# VNP.net
KiCad netlist of a schematic drawn in EAGLE
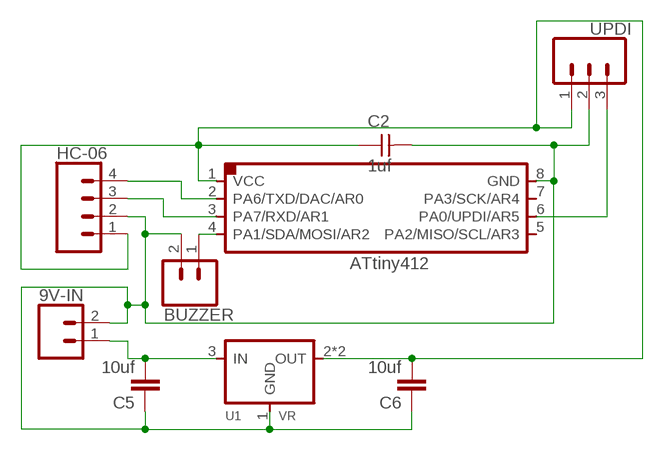
[diagram p0: schematic, sheet 1]

(export (version "E")
  (design (tool "Eeschema 10.0.6"))
  (components
    (comp (ref "9V-IN")
      (value "CONN_02PTH3")
      (footprint "eagle-import:1X02_LONGPADS")
      (libsource (lib "eagle-import") (part "CONN_02PTH3"))
    )
    (comp (ref "BUZZER")
      (value "CONN_02LOCK_LONGPADS")
      (footprint "eagle-import:1X02_LOCK_LONGPADS")
      (libsource (lib "eagle-import") (part "CONN_02LOCK_LONGPADS"))
    )
    (comp (ref "C2")
      (value "1uf")
      (footprint "eagle-import:C1206")
      (libsource (lib "eagle-import") (part "CAP_UNPOLARIZED"))
    )
    (comp (ref "C5")
      (value "10uf")
      (footprint "eagle-import:1206")
      (libsource (lib "eagle-import") (part "CAP1206"))
    )
    (comp (ref "C6")
      (value "10uf")
      (footprint "eagle-import:1206")
      (libsource (lib "eagle-import") (part "CAP1206"))
    )
    (comp (ref "HC-06")
      (value "CONN_04POLAR")
      (footprint "eagle-import:MOLEX-1X4")
      (libsource (lib "eagle-import") (part "CONN_04POLAR"))
    )
    (comp (ref "U$1")
      (value "UC_ATTINY412SI")
      (footprint "eagle-import:SOIC8")
      (libsource (lib "eagle-import") (part "UC_ATTINY412SI"))
    )
    (comp (ref "U1")
      (value "VR")
      (footprint "eagle-import:SOT223")
      (libsource (lib "eagle-import") (part "VR_REGULATOR_SOT223"))
    )
    (comp (ref "UPDI")
      (value "CONN_03SMD_RA_MALE")
      (footprint "eagle-import:1X03_SMD_RA_MALE")
      (libsource (lib "eagle-import") (part "CONN_03SMD_RA_MALE"))
    )
  )
  (nets
    (net (code "1") (name "Net-(U$1-GND)") (class "Default")
      (node (ref "9V-IN") (pin "2") (pinfunction "2_2") (pintype "passive"))
      (node (ref "BUZZER") (pin "2") (pinfunction "2_2") (pintype "passive"))
      (node (ref "C2") (pin "2") (pinfunction "2_2") (pintype "passive"))
      (node (ref "C5") (pin "1") (pinfunction "1_1") (pintype "passive"))
      (node (ref "C6") (pin "1") (pinfunction "1_1") (pintype "passive"))
      (node (ref "HC-06") (pin "2") (pinfunction "2_2") (pintype "passive"))
      (node (ref "U$1") (pin "8") (pinfunction "GND_8") (pintype "bidirectional"))
      (node (ref "U1") (pin "1") (pinfunction "GND_1") (pintype "bidirectional"))
      (node (ref "UPDI") (pin "2") (pinfunction "2_2") (pintype "passive"))
    )
    (net (code "2") (name "Net-(U$1-PA0{slash}UPDI{slash}AR5)") (class "Default")
      (node (ref "U$1") (pin "6") (pinfunction "PA0/UPDI/AR5_6") (pintype "bidirectional"))
      (node (ref "UPDI") (pin "3") (pinfunction "3_3") (pintype "passive"))
    )
    (net (code "3") (name "Net-(U$1-PA1{slash}SDA{slash}MOSI{slash}AR2)") (class "Default")
      (node (ref "BUZZER") (pin "1") (pinfunction "1_1") (pintype "passive"))
      (node (ref "U$1") (pin "4") (pinfunction "PA1/SDA/MOSI/AR2_4") (pintype "bidirectional"))
    )
    (net (code "4") (name "Net-(U$1-PA6{slash}TXD{slash}DAC{slash}AR0)") (class "Default")
      (node (ref "HC-06") (pin "4") (pinfunction "4_4") (pintype "passive"))
      (node (ref "U$1") (pin "2") (pinfunction "PA6/TXD/DAC/AR0_2") (pintype "bidirectional"))
    )
    (net (code "5") (name "Net-(U$1-PA7{slash}RXD{slash}AR1)") (class "Default")
      (node (ref "HC-06") (pin "3") (pinfunction "3_3") (pintype "passive"))
      (node (ref "U$1") (pin "3") (pinfunction "PA7/RXD/AR1_3") (pintype "bidirectional"))
    )
    (net (code "6") (name "Net-(U$1-VCC)") (class "Default")
      (node (ref "C2") (pin "1") (pinfunction "1_1") (pintype "passive"))
      (node (ref "C6") (pin "2") (pinfunction "2_2") (pintype "passive"))
      (node (ref "HC-06") (pin "1") (pinfunction "1_1") (pintype "passive"))
      (node (ref "U$1") (pin "1") (pinfunction "VCC_1") (pintype "bidirectional"))
      (node (ref "U1") (pin "2") (pinfunction "OUT_2") (pintype "bidirectional"))
      (node (ref "U1") (pin "4") (pinfunction "OUT_4") (pintype "bidirectional"))
      (node (ref "UPDI") (pin "1") (pinfunction "1_1") (pintype "passive"))
    )
    (net (code "7") (name "Net-(U1-IN)") (class "Default")
      (node (ref "9V-IN") (pin "1") (pinfunction "1_1") (pintype "passive"))
      (node (ref "C5") (pin "2") (pinfunction "2_2") (pintype "passive"))
      (node (ref "U1") (pin "3") (pinfunction "IN_3") (pintype "bidirectional"))
    )
    (net (code "8") (name "unconnected-(U$1-PA2{slash}MISO{slash}SCL{slash}AR3-Pad5)") (class "Default")
      (node (ref "U$1") (pin "5") (pinfunction "PA2/MISO/SCL/AR3_5") (pintype "bidirectional"))
    )
    (net (code "9") (name "unconnected-(U$1-PA3{slash}SCK{slash}AR4-Pad7)") (class "Default")
      (node (ref "U$1") (pin "7") (pinfunction "PA3/SCK/AR4_7") (pintype "bidirectional"))
    )
  )
)
